# ESC_IMU.net
KiCad netlist of a schematic drawn in Altium Designer
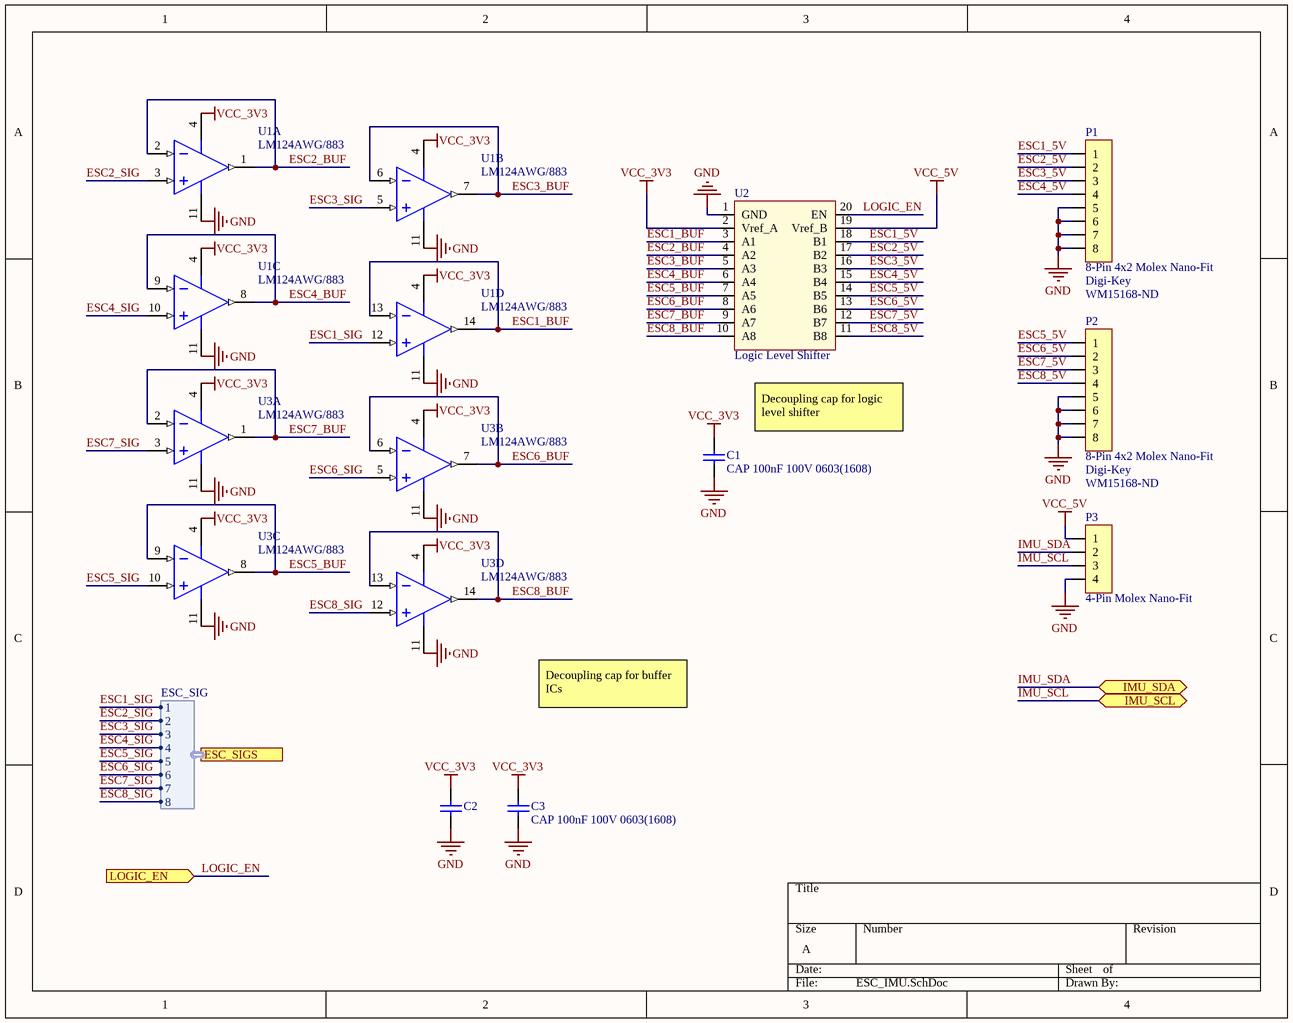
[diagram p0: ESC_IMU.SchDoc]

(export (version "E")
  (design (tool "Eeschema 10.0.6"))
  (components
    (comp (ref "C1")
      (value "CAP 100nF 100V 0603(1608)")
      (footprint "CAPC0603(1608)100_L")
      (description "CAP 100nF 100V ±10% 0603 (1608 Metric) Thickness 1mm SMD")
      (fields (field (name "TOLERANCE") "Â±10%"))
      (libsource (lib "Altium Content Vault") (part "CAP"))
    )
    (comp (ref "C2")
      (value "CAP 100nF 100V 0603(1608)")
      (footprint "CAPC0603(1608)100_L")
      (description "CAP 100nF 100V ±10% 0603 (1608 Metric) Thickness 1mm SMD")
      (fields (field (name "TOLERANCE") "Â±10%"))
      (libsource (lib "Altium Content Vault") (part "CAP"))
    )
    (comp (ref "C3")
      (value "CAP 100nF 100V 0603(1608)")
      (footprint "CAPC0603(1608)100_L")
      (description "CAP 100nF 100V ±10% 0603 (1608 Metric) Thickness 1mm SMD")
      (fields (field (name "TOLERANCE") "Â±10%"))
      (libsource (lib "Altium Content Vault") (part "CAP"))
    )
    (comp (ref "P1")
      (value "8-Pin 4x2 Molex Nano-Fit")
      (footprint "MOLEX NANO-FIT 2x4")
      (description "NanoFit RA Hdr TH DR 8Ckt")
      (fields
        (field (name "PART NUMBER") "105314-1216")
        (field (name "MANUFACTURER") "Molex")
        (field (name "SUPPLIER 1") "Digi-Key")
        (field (name "SUPPLIER PART NUMBER 1") "WM15168-ND")
      )
      (libsource (lib "CMR_Connectors") (part "8-Pin 2-Row Nano-Fit"))
    )
    (comp (ref "P2")
      (value "8-Pin 4x2 Molex Nano-Fit")
      (footprint "MOLEX NANO-FIT 2x4")
      (description "NanoFit RA Hdr TH DR 8Ckt")
      (fields
        (field (name "PART NUMBER") "105314-1216")
        (field (name "MANUFACTURER") "Molex")
        (field (name "SUPPLIER 1") "Digi-Key")
        (field (name "SUPPLIER PART NUMBER 1") "WM15168-ND")
      )
      (libsource (lib "CMR_Connectors") (part "8-Pin 2-Row Nano-Fit"))
    )
    (comp (ref "P3")
      (value "4-Pin Molex Nano-Fit")
      (footprint "MOLEX NANO-FIT 1X4")
      (description "NanoFit RA Hdr TH SR 4Ckt")
      (fields (field (name "MANUFACTURER") "Molex") (field (name "PART NUMBER") "105313-1204"))
      (libsource (lib "CMR_Connectors") (part "4-Pin Nano-Fit"))
    )
    (comp (ref "U1")
      (value "LM124AWG/883")
      (footprint "NAC0014A_L")
      (description "Low Power Quad Operational Amplifier, 14-pin CerPACK")
      (fields (field (name "MANUFACTURER") "Texas Instruments"))
      (libsource (lib "Altium Content Vault") (part "AMP-OPA-LM124-14"))
    )
    (comp (ref "U2")
      (value "Logic Level Shifter")
      (footprint "TSOP65P640X120-20N")
      (libsource (lib "CMR_ICs") (part "TI LSF0108-Q1"))
    )
    (comp (ref "U3")
      (value "LM124AWG/883")
      (footprint "NAC0014A_L")
      (description "Low Power Quad Operational Amplifier, 14-pin CerPACK")
      (fields (field (name "MANUFACTURER") "Texas Instruments"))
      (libsource (lib "Altium Content Vault") (part "AMP-OPA-LM124-14"))
    )
  )
  (nets
    (net (code "2") (name "/ESC1_5V") (class "Default")
      (node (ref "P1") (pin "1") (pinfunction "1_1") (pintype "passive"))
      (node (ref "U2") (pin "18") (pinfunction "B1_18") (pintype "passive"))
    )
    (net (code "3") (name "/ESC1_BUF") (class "Default")
      (node (ref "U1") (pin "13") (pinfunction "IN4-_13") (pintype "input"))
      (node (ref "U1") (pin "14") (pinfunction "OUT4_14") (pintype "output"))
      (node (ref "U2") (pin "3") (pinfunction "A1_3") (pintype "passive"))
    )
    (net (code "4") (name "/ESC1_SIG") (class "Default")
      (node (ref "U1") (pin "12") (pinfunction "IN4+_12") (pintype "input"))
    )
    (net (code "5") (name "/ESC2_5V") (class "Default")
      (node (ref "P1") (pin "2") (pinfunction "2_2") (pintype "passive"))
      (node (ref "U2") (pin "17") (pinfunction "B2_17") (pintype "passive"))
    )
    (net (code "6") (name "/ESC2_BUF") (class "Default")
      (node (ref "U1") (pin "1") (pinfunction "OUT1_1") (pintype "output"))
      (node (ref "U1") (pin "2") (pinfunction "IN1-_2") (pintype "input"))
      (node (ref "U2") (pin "4") (pinfunction "A2_4") (pintype "passive"))
    )
    (net (code "7") (name "/ESC2_SIG") (class "Default")
      (node (ref "U1") (pin "3") (pinfunction "IN1+_3") (pintype "input"))
    )
    (net (code "8") (name "/ESC3_5V") (class "Default")
      (node (ref "P1") (pin "3") (pinfunction "3_3") (pintype "passive"))
      (node (ref "U2") (pin "16") (pinfunction "B3_16") (pintype "passive"))
    )
    (net (code "9") (name "/ESC3_BUF") (class "Default")
      (node (ref "U1") (pin "6") (pinfunction "IN2-_6") (pintype "input"))
      (node (ref "U1") (pin "7") (pinfunction "OUT2_7") (pintype "output"))
      (node (ref "U2") (pin "5") (pinfunction "A3_5") (pintype "passive"))
    )
    (net (code "10") (name "/ESC3_SIG") (class "Default")
      (node (ref "U1") (pin "5") (pinfunction "IN2+_5") (pintype "input"))
    )
    (net (code "11") (name "/ESC4_5V") (class "Default")
      (node (ref "P1") (pin "4") (pinfunction "4_4") (pintype "passive"))
      (node (ref "U2") (pin "15") (pinfunction "B4_15") (pintype "passive"))
    )
    (net (code "12") (name "/ESC4_BUF") (class "Default")
      (node (ref "U1") (pin "8") (pinfunction "OUT3_8") (pintype "output"))
      (node (ref "U1") (pin "9") (pinfunction "IN3-_9") (pintype "input"))
      (node (ref "U2") (pin "6") (pinfunction "A4_6") (pintype "passive"))
    )
    (net (code "13") (name "/ESC4_SIG") (class "Default")
      (node (ref "U1") (pin "10") (pinfunction "IN3+_10") (pintype "input"))
    )
    (net (code "14") (name "/ESC5_5V") (class "Default")
      (node (ref "P2") (pin "1") (pinfunction "1_1") (pintype "passive"))
      (node (ref "U2") (pin "14") (pinfunction "B5_14") (pintype "passive"))
    )
    (net (code "15") (name "/ESC5_BUF") (class "Default")
      (node (ref "U2") (pin "7") (pinfunction "A5_7") (pintype "passive"))
      (node (ref "U3") (pin "8") (pinfunction "OUT3_8") (pintype "output"))
      (node (ref "U3") (pin "9") (pinfunction "IN3-_9") (pintype "input"))
    )
    (net (code "16") (name "/ESC5_SIG") (class "Default")
      (node (ref "U3") (pin "10") (pinfunction "IN3+_10") (pintype "input"))
    )
    (net (code "17") (name "/ESC6_5V") (class "Default")
      (node (ref "P2") (pin "2") (pinfunction "2_2") (pintype "passive"))
      (node (ref "U2") (pin "13") (pinfunction "B6_13") (pintype "passive"))
    )
    (net (code "18") (name "/ESC6_BUF") (class "Default")
      (node (ref "U2") (pin "8") (pinfunction "A6_8") (pintype "passive"))
      (node (ref "U3") (pin "6") (pinfunction "IN2-_6") (pintype "input"))
      (node (ref "U3") (pin "7") (pinfunction "OUT2_7") (pintype "output"))
    )
    (net (code "19") (name "/ESC6_SIG") (class "Default")
      (node (ref "U3") (pin "5") (pinfunction "IN2+_5") (pintype "input"))
    )
    (net (code "20") (name "/ESC7_5V") (class "Default")
      (node (ref "P2") (pin "3") (pinfunction "3_3") (pintype "passive"))
      (node (ref "U2") (pin "12") (pinfunction "B7_12") (pintype "passive"))
    )
    (net (code "21") (name "/ESC7_BUF") (class "Default")
      (node (ref "U2") (pin "9") (pinfunction "A7_9") (pintype "passive"))
      (node (ref "U3") (pin "1") (pinfunction "OUT1_1") (pintype "output"))
      (node (ref "U3") (pin "2") (pinfunction "IN1-_2") (pintype "input"))
    )
    (net (code "22") (name "/ESC7_SIG") (class "Default")
      (node (ref "U3") (pin "3") (pinfunction "IN1+_3") (pintype "input"))
    )
    (net (code "23") (name "/ESC8_5V") (class "Default")
      (node (ref "P2") (pin "4") (pinfunction "4_4") (pintype "passive"))
      (node (ref "U2") (pin "11") (pinfunction "B8_11") (pintype "passive"))
    )
    (net (code "24") (name "/ESC8_BUF") (class "Default")
      (node (ref "U2") (pin "10") (pinfunction "A8_10") (pintype "passive"))
      (node (ref "U3") (pin "13") (pinfunction "IN4-_13") (pintype "input"))
      (node (ref "U3") (pin "14") (pinfunction "OUT4_14") (pintype "output"))
    )
    (net (code "25") (name "/ESC8_SIG") (class "Default")
      (node (ref "U3") (pin "12") (pinfunction "IN4+_12") (pintype "input"))
    )
    (net (code "26") (name "/IMU_SCL") (class "Default")
      (node (ref "P3") (pin "3") (pinfunction "3_3") (pintype "passive"))
    )
    (net (code "27") (name "/IMU_SDA") (class "Default")
      (node (ref "P3") (pin "2") (pinfunction "2_2") (pintype "passive"))
    )
    (net (code "28") (name "/LOGIC_EN") (class "Default")
      (node (ref "U2") (pin "20") (pinfunction "EN_20") (pintype "passive"))
    )
    (net (code "30") (name "GND") (class "Default")
      (node (ref "C1") (pin "2") (pinfunction "2_2") (pintype "passive"))
      (node (ref "C2") (pin "2") (pinfunction "2_2") (pintype "passive"))
      (node (ref "C3") (pin "2") (pinfunction "2_2") (pintype "passive"))
      (node (ref "P1") (pin "5") (pinfunction "5_5") (pintype "passive"))
      (node (ref "P1") (pin "6") (pinfunction "6_6") (pintype "passive"))
      (node (ref "P1") (pin "7") (pinfunction "7_7") (pintype "passive"))
      (node (ref "P1") (pin "8") (pinfunction "8_8") (pintype "passive"))
      (node (ref "P2") (pin "5") (pinfunction "5_5") (pintype "passive"))
      (node (ref "P2") (pin "6") (pinfunction "6_6") (pintype "passive"))
      (node (ref "P2") (pin "7") (pinfunction "7_7") (pintype "passive"))
      (node (ref "P2") (pin "8") (pinfunction "8_8") (pintype "passive"))
      (node (ref "P3") (pin "4") (pinfunction "4_4") (pintype "passive"))
      (node (ref "U1") (pin "11") (pinfunction "GND_11") (pintype "power_in"))
      (node (ref "U2") (pin "1") (pinfunction "GND_1") (pintype "passive"))
      (node (ref "U3") (pin "11") (pinfunction "GND_11") (pintype "power_in"))
    )
    (net (code "31") (name "VCC_3V3") (class "Default")
      (node (ref "C1") (pin "1") (pinfunction "1_1") (pintype "passive"))
      (node (ref "C2") (pin "1") (pinfunction "1_1") (pintype "passive"))
      (node (ref "C3") (pin "1") (pinfunction "1_1") (pintype "passive"))
      (node (ref "U1") (pin "4") (pinfunction "V+_4") (pintype "power_in"))
      (node (ref "U2") (pin "2") (pinfunction "Vref_A_2") (pintype "passive"))
      (node (ref "U3") (pin "4") (pinfunction "V+_4") (pintype "power_in"))
    )
    (net (code "32") (name "VCC_5V") (class "Default")
      (node (ref "P3") (pin "1") (pinfunction "1_1") (pintype "passive"))
      (node (ref "U2") (pin "19") (pinfunction "Vref_B_19") (pintype "passive"))
    )
  )
)
